# icp_rocker.net
KiCad netlist of a schematic drawn in EAGLE
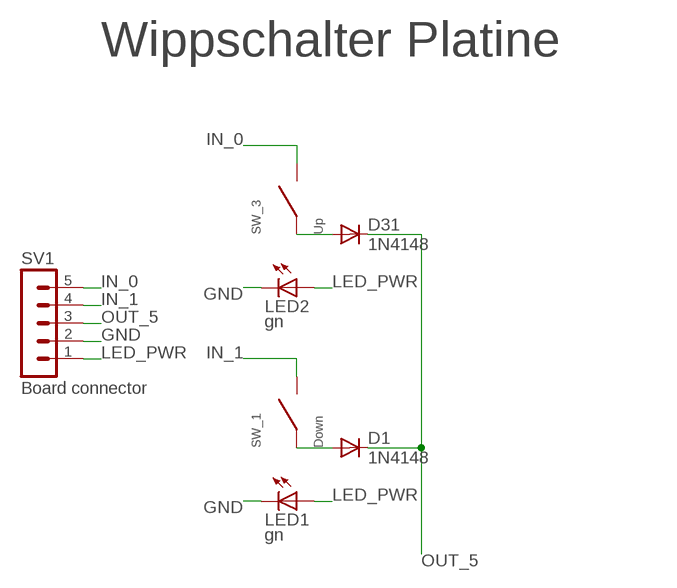
[diagram p0: schematic, sheet 1]

(export (version "E")
  (design (tool "Eeschema 10.0.6"))
  (components
    (comp (ref "D1")
      (value "1N4148")
      (footprint "eagle-import:DO35-10")
      (libsource (lib "eagle-import") (part "DIODE-DO35-10"))
    )
    (comp (ref "D31")
      (value "1N4148")
      (footprint "eagle-import:DO35-10")
      (libsource (lib "eagle-import") (part "DIODE-DO35-10"))
    )
    (comp (ref "LED1")
      (value "gn")
      (footprint "eagle-import:CHIPLED_1206")
      (libsource (lib "eagle-import") (part "LEDCHIPLED_1206"))
    )
    (comp (ref "LED2")
      (value "gn")
      (footprint "eagle-import:CHIPLED_1206")
      (libsource (lib "eagle-import") (part "LEDCHIPLED_1206"))
    )
    (comp (ref "SV1")
      (value "Board connector")
      (footprint "eagle-import:MA05-1")
      (libsource (lib "eagle-import") (part "MA05-1"))
    )
    (comp (ref "SW_1")
      (value "Down")
      (footprint "eagle-import:TYPE_A")
      (libsource (lib "eagle-import") (part "APEM_SWITCH"))
    )
    (comp (ref "SW_3")
      (value "Up")
      (footprint "eagle-import:TYPE_A")
      (libsource (lib "eagle-import") (part "APEM_SWITCH"))
    )
  )
  (nets
    (net (code "1") (name "/GND") (class "Default")
      (node (ref "LED1") (pin "C") (pinfunction "C_C") (pintype "passive"))
      (node (ref "LED2") (pin "C") (pinfunction "C_C") (pintype "passive"))
      (node (ref "SV1") (pin "2") (pinfunction "2_2") (pintype "passive"))
    )
    (net (code "2") (name "/IN_0") (class "Default")
      (node (ref "SV1") (pin "5") (pinfunction "5_5") (pintype "passive"))
      (node (ref "SW_3") (pin "P$1") (pinfunction "P$1_P$1") (pintype "passive"))
    )
    (net (code "3") (name "/IN_1") (class "Default")
      (node (ref "SV1") (pin "4") (pinfunction "4_4") (pintype "passive"))
      (node (ref "SW_1") (pin "P$1") (pinfunction "P$1_P$1") (pintype "passive"))
    )
    (net (code "4") (name "/LED_PWR") (class "Default")
      (node (ref "LED1") (pin "A") (pinfunction "A_A") (pintype "passive"))
      (node (ref "LED2") (pin "A") (pinfunction "A_A") (pintype "passive"))
      (node (ref "SV1") (pin "1") (pinfunction "1_1") (pintype "passive"))
    )
    (net (code "5") (name "/OUT_5") (class "Default")
      (node (ref "D1") (pin "C") (pinfunction "C_C") (pintype "passive"))
      (node (ref "D31") (pin "C") (pinfunction "C_C") (pintype "passive"))
      (node (ref "SV1") (pin "3") (pinfunction "3_3") (pintype "passive"))
    )
    (net (code "6") (name "Net-(D1-PadA)") (class "Default")
      (node (ref "D1") (pin "A") (pinfunction "A_A") (pintype "passive"))
      (node (ref "SW_1") (pin "P$2") (pinfunction "P$2_P$2") (pintype "passive"))
    )
    (net (code "7") (name "Net-(D31-PadA)") (class "Default")
      (node (ref "D31") (pin "A") (pinfunction "A_A") (pintype "passive"))
      (node (ref "SW_3") (pin "P$2") (pinfunction "P$2_P$2") (pintype "passive"))
    )
  )
)
